# UNOSMD_V11.net
KiCad netlist of a schematic drawn in EAGLE
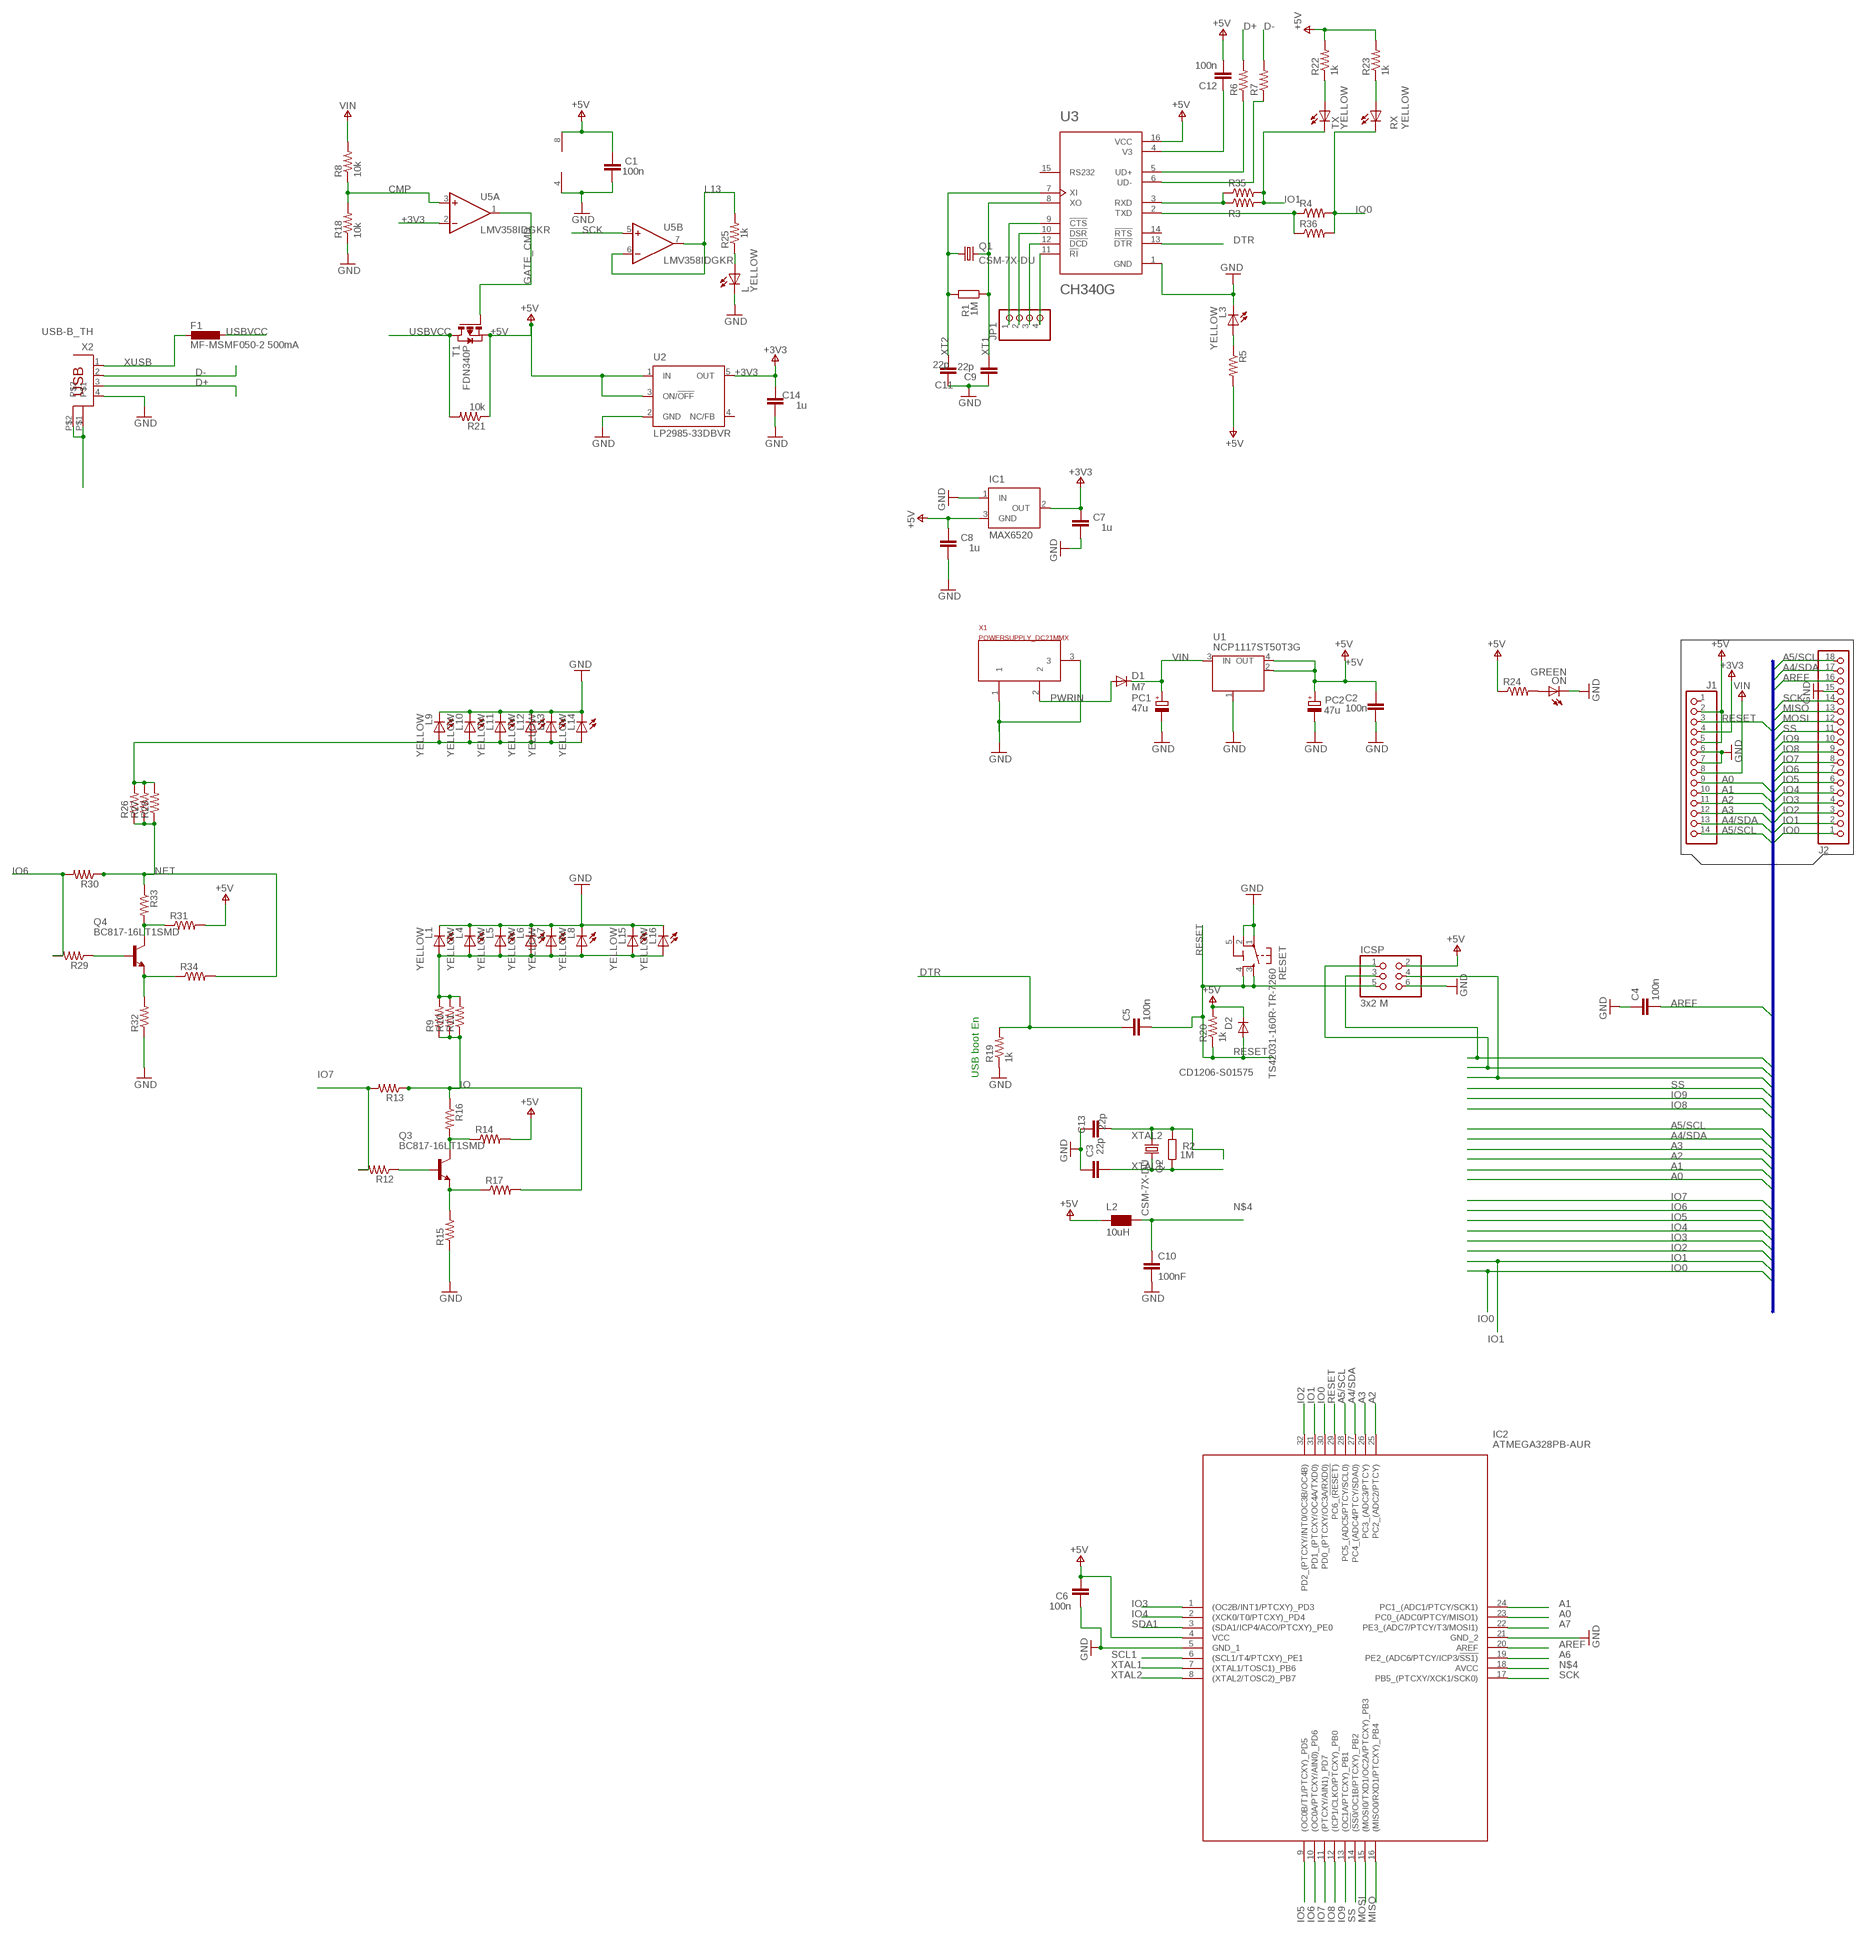
[diagram p0: schematic, sheet 1]

(export (version "E")
  (design (tool "Eeschema 10.0.6"))
  (components
    (comp (ref "C1")
      (value "100n")
      (footprint "eagle-import:C0603-ROUND")
      (libsource (lib "eagle-import") (part "C-EU0603-RND"))
    )
    (comp (ref "C2")
      (value "100n")
      (footprint "eagle-import:C0603-ROUND")
      (libsource (lib "eagle-import") (part "C-EU0603-RND"))
    )
    (comp (ref "C3")
      (value "22p")
      (footprint "eagle-import:C0603-ROUND")
      (libsource (lib "eagle-import") (part "C-EU0603-RND"))
    )
    (comp (ref "C4")
      (value "100n")
      (footprint "eagle-import:C0603-ROUND")
      (libsource (lib "eagle-import") (part "C-EU0603-RND"))
    )
    (comp (ref "C5")
      (value "100n")
      (footprint "eagle-import:C0603-ROUND")
      (libsource (lib "eagle-import") (part "C-EU0603-RND"))
    )
    (comp (ref "C6")
      (value "100n")
      (footprint "eagle-import:C0603-ROUND")
      (libsource (lib "eagle-import") (part "C-EU0603-RND"))
    )
    (comp (ref "C7")
      (value "1u")
      (footprint "eagle-import:C0603-ROUND")
      (libsource (lib "eagle-import") (part "C-EU0603-RND"))
    )
    (comp (ref "C8")
      (value "1u")
      (footprint "eagle-import:C0603-ROUND")
      (libsource (lib "eagle-import") (part "C-EU0603-RND"))
    )
    (comp (ref "C9")
      (value "22p")
      (footprint "eagle-import:C0603-ROUND")
      (libsource (lib "eagle-import") (part "C-EU0603-RND"))
    )
    (comp (ref "C10")
      (value "100nF")
      (footprint "eagle-import:C0603-ROUND")
      (fields (field (name "PART_NUMBER") "100nF_0603"))
      (libsource (lib "eagle-import") (part "0015_100NF_0603"))
    )
    (comp (ref "C11")
      (value "22p")
      (footprint "eagle-import:C0603-ROUND")
      (libsource (lib "eagle-import") (part "C-EU0603-RND"))
    )
    (comp (ref "C12")
      (value "100n")
      (footprint "eagle-import:C0603-ROUND")
      (libsource (lib "eagle-import") (part "C-EU0603-RND"))
    )
    (comp (ref "C13")
      (value "22p")
      (footprint "eagle-import:C0603-ROUND")
      (libsource (lib "eagle-import") (part "C-EU0603-RND"))
    )
    (comp (ref "C14")
      (value "1u")
      (footprint "eagle-import:C0603-ROUND")
      (libsource (lib "eagle-import") (part "C-EU0603-RND"))
    )
    (comp (ref "D1")
      (value "M7")
      (footprint "eagle-import:SMB")
      (libsource (lib "eagle-import") (part "DIODE-SMB"))
    )
    (comp (ref "D2")
      (value "CD1206-S01575")
      (footprint "eagle-import:MINIMELF")
      (libsource (lib "eagle-import") (part "DIODE-MINIMELF"))
    )
    (comp (ref "F1")
      (value "MF-MSMF050-2 500mA")
      (footprint "eagle-import:L1812")
      (libsource (lib "eagle-import") (part "L-EUL1812"))
    )
    (comp (ref "IC1")
      (value "MAX6520")
      (footprint "eagle-import:SOT23")
      (fields (field (name "MF") "MAXIM") (field (name "MPN") "MAX6520EUR-T"))
      (libsource (lib "eagle-import") (part "MAX6520"))
    )
    (comp (ref "IC2")
      (value "ATMEGA328PB-AUR")
      (footprint "eagle-import:QFP80P900X900X120-32N")
      (fields (field (name "MOUSER_PART_NUMBER") "556-ATMEGA328PB-AUR"))
      (libsource (lib "eagle-import") (part "ATMEGA328PB-AUR"))
    )
    (comp (ref "ICSP")
      (value "3x2 M")
      (footprint "eagle-import:2X03")
      (libsource (lib "eagle-import") (part "PINHD-2X3"))
    )
    (comp (ref "J1")
      (value "-")
      (footprint "eagle-import:1X14-CUSTOM")
      (libsource (lib "eagle-import") (part "PINHD-1X14-CUSTOM"))
    )
    (comp (ref "J2")
      (value "-")
      (footprint "eagle-import:1X18-CUSTOM")
      (libsource (lib "eagle-import") (part "PINHD-1X18"))
    )
    (comp (ref "JP1")
      (value "PINHD-1X4")
      (footprint "eagle-import:1X04")
      (libsource (lib "eagle-import") (part "PINHD-1X4"))
    )
    (comp (ref "L")
      (value "YELLOW")
      (footprint "eagle-import:CHIP-LED0805")
      (libsource (lib "eagle-import") (part "LEDCHIP-LED0805"))
    )
    (comp (ref "L1")
      (value "YELLOW")
      (footprint "eagle-import:CHIP-LED0805")
      (libsource (lib "eagle-import") (part "LEDCHIP-LED0805"))
    )
    (comp (ref "L2")
      (value "10uH")
      (footprint "eagle-import:0805")
      (fields (field (name "PART_NUMBER") "CV201210-100K"))
      (libsource (lib "eagle-import") (part "0715_CV201210-100K"))
    )
    (comp (ref "L3")
      (value "YELLOW")
      (footprint "eagle-import:CHIP-LED0805")
      (libsource (lib "eagle-import") (part "LEDCHIP-LED0805"))
    )
    (comp (ref "L4")
      (value "YELLOW")
      (footprint "eagle-import:CHIP-LED0805")
      (libsource (lib "eagle-import") (part "LEDCHIP-LED0805"))
    )
    (comp (ref "L5")
      (value "YELLOW")
      (footprint "eagle-import:CHIP-LED0805")
      (libsource (lib "eagle-import") (part "LEDCHIP-LED0805"))
    )
    (comp (ref "L6")
      (value "YELLOW")
      (footprint "eagle-import:CHIP-LED0805")
      (libsource (lib "eagle-import") (part "LEDCHIP-LED0805"))
    )
    (comp (ref "L7")
      (value "YELLOW")
      (footprint "eagle-import:CHIP-LED0805")
      (libsource (lib "eagle-import") (part "LEDCHIP-LED0805"))
    )
    (comp (ref "L8")
      (value "YELLOW")
      (footprint "eagle-import:CHIP-LED0805")
      (libsource (lib "eagle-import") (part "LEDCHIP-LED0805"))
    )
    (comp (ref "L9")
      (value "YELLOW")
      (footprint "eagle-import:CHIP-LED0805")
      (libsource (lib "eagle-import") (part "LEDCHIP-LED0805"))
    )
    (comp (ref "L10")
      (value "YELLOW")
      (footprint "eagle-import:CHIP-LED0805")
      (libsource (lib "eagle-import") (part "LEDCHIP-LED0805"))
    )
    (comp (ref "L11")
      (value "YELLOW")
      (footprint "eagle-import:CHIP-LED0805")
      (libsource (lib "eagle-import") (part "LEDCHIP-LED0805"))
    )
    (comp (ref "L12")
      (value "YELLOW")
      (footprint "eagle-import:CHIP-LED0805")
      (libsource (lib "eagle-import") (part "LEDCHIP-LED0805"))
    )
    (comp (ref "L13")
      (value "YELLOW")
      (footprint "eagle-import:CHIP-LED0805")
      (libsource (lib "eagle-import") (part "LEDCHIP-LED0805"))
    )
    (comp (ref "L14")
      (value "YELLOW")
      (footprint "eagle-import:CHIP-LED0805")
      (libsource (lib "eagle-import") (part "LEDCHIP-LED0805"))
    )
    (comp (ref "L15")
      (value "YELLOW")
      (footprint "eagle-import:CHIP-LED0805")
      (libsource (lib "eagle-import") (part "LEDCHIP-LED0805"))
    )
    (comp (ref "L16")
      (value "YELLOW")
      (footprint "eagle-import:CHIP-LED0805")
      (libsource (lib "eagle-import") (part "LEDCHIP-LED0805"))
    )
    (comp (ref "ON")
      (value "GREEN")
      (footprint "eagle-import:CHIP-LED0805")
      (libsource (lib "eagle-import") (part "LEDCHIP-LED0805"))
    )
    (comp (ref "PC1")
      (value "47u")
      (footprint "eagle-import:PANASONIC_D")
      (libsource (lib "eagle-import") (part "CPOL-EUD"))
    )
    (comp (ref "PC2")
      (value "47u")
      (footprint "eagle-import:PANASONIC_D")
      (libsource (lib "eagle-import") (part "CPOL-EUD"))
    )
    (comp (ref "Q1")
      (value "CSM-7X-DU")
      (footprint "eagle-import:CSM-7X-DU")
      (libsource (lib "eagle-import") (part "CSM-7X-DU"))
    )
    (comp (ref "Q2")
      (value "CSM-7X-DU")
      (footprint "eagle-import:CSM-7X-DU")
      (libsource (lib "eagle-import") (part "CSM-7X-DU"))
    )
    (comp (ref "Q3")
      (value "BC817-16LT1SMD")
      (footprint "eagle-import:SOT23-BEC")
      (libsource (lib "eagle-import") (part "BC817SMD-16LT1"))
    )
    (comp (ref "Q4")
      (value "BC817-16LT1SMD")
      (footprint "eagle-import:SOT23-BEC")
      (libsource (lib "eagle-import") (part "BC817SMD-16LT1"))
    )
    (comp (ref "R1")
      (value "1M")
      (footprint "eagle-import:R0603-ROUND")
      (libsource (lib "eagle-import") (part "R-EU_R0603"))
    )
    (comp (ref "R2")
      (value "1M")
      (footprint "eagle-import:R0603-ROUND")
      (libsource (lib "eagle-import") (part "R-EU_R0603"))
    )
    (comp (ref "R3")
      (value "R-US_R0603")
      (footprint "eagle-import:R0603")
      (libsource (lib "eagle-import") (part "R-US_R0603"))
    )
    (comp (ref "R4")
      (value "R-US_R0603")
      (footprint "eagle-import:R0603")
      (libsource (lib "eagle-import") (part "R-US_R0603"))
    )
    (comp (ref "R5")
      (value "R-US_R0603")
      (footprint "eagle-import:R0603")
      (libsource (lib "eagle-import") (part "R-US_R0603"))
    )
    (comp (ref "R6")
      (value "R-US_R0603")
      (footprint "eagle-import:R0603")
      (libsource (lib "eagle-import") (part "R-US_R0603"))
    )
    (comp (ref "R7")
      (value "R-US_R0603")
      (footprint "eagle-import:R0603")
      (libsource (lib "eagle-import") (part "R-US_R0603"))
    )
    (comp (ref "R8")
      (value "10k")
      (footprint "eagle-import:R0603")
      (libsource (lib "eagle-import") (part "R-US_R0603"))
    )
    (comp (ref "R9")
      (value "R-US_R0603")
      (footprint "eagle-import:R0603")
      (libsource (lib "eagle-import") (part "R-US_R0603"))
    )
    (comp (ref "R10")
      (value "R-US_R0603")
      (footprint "eagle-import:R0603")
      (libsource (lib "eagle-import") (part "R-US_R0603"))
    )
    (comp (ref "R11")
      (value "R-US_R0603")
      (footprint "eagle-import:R0603")
      (libsource (lib "eagle-import") (part "R-US_R0603"))
    )
    (comp (ref "R12")
      (value "R-US_R0603")
      (footprint "eagle-import:R0603")
      (libsource (lib "eagle-import") (part "R-US_R0603"))
    )
    (comp (ref "R13")
      (value "R-US_R0603")
      (footprint "eagle-import:R0603")
      (libsource (lib "eagle-import") (part "R-US_R0603"))
    )
    (comp (ref "R14")
      (value "R-US_R0603")
      (footprint "eagle-import:R0603")
      (libsource (lib "eagle-import") (part "R-US_R0603"))
    )
    (comp (ref "R15")
      (value "R-US_R0603")
      (footprint "eagle-import:R0603")
      (libsource (lib "eagle-import") (part "R-US_R0603"))
    )
    (comp (ref "R16")
      (value "R-US_R0603")
      (footprint "eagle-import:R0603")
      (libsource (lib "eagle-import") (part "R-US_R0603"))
    )
    (comp (ref "R17")
      (value "R-US_R0603")
      (footprint "eagle-import:R0603")
      (libsource (lib "eagle-import") (part "R-US_R0603"))
    )
    (comp (ref "R18")
      (value "10k")
      (footprint "eagle-import:R0603")
      (libsource (lib "eagle-import") (part "R-US_R0603"))
    )
    (comp (ref "R19")
      (value "1k")
      (footprint "eagle-import:R0603")
      (libsource (lib "eagle-import") (part "R-US_R0603"))
    )
    (comp (ref "R20")
      (value "1k")
      (footprint "eagle-import:R0603")
      (libsource (lib "eagle-import") (part "R-US_R0603"))
    )
    (comp (ref "R21")
      (value "10k")
      (footprint "eagle-import:R0603")
      (libsource (lib "eagle-import") (part "R-US_R0603"))
    )
    (comp (ref "R22")
      (value "1k")
      (footprint "eagle-import:R0603")
      (libsource (lib "eagle-import") (part "R-US_R0603"))
    )
    (comp (ref "R23")
      (value "1k")
      (footprint "eagle-import:R0603")
      (libsource (lib "eagle-import") (part "R-US_R0603"))
    )
    (comp (ref "R24")
      (value "R-US_R0603")
      (footprint "eagle-import:R0603")
      (libsource (lib "eagle-import") (part "R-US_R0603"))
    )
    (comp (ref "R25")
      (value "1k")
      (footprint "eagle-import:R0603")
      (libsource (lib "eagle-import") (part "R-US_R0603"))
    )
    (comp (ref "R26")
      (value "R-US_R0603")
      (footprint "eagle-import:R0603")
      (libsource (lib "eagle-import") (part "R-US_R0603"))
    )
    (comp (ref "R27")
      (value "R-US_R0603")
      (footprint "eagle-import:R0603")
      (libsource (lib "eagle-import") (part "R-US_R0603"))
    )
    (comp (ref "R28")
      (value "R-US_R0603")
      (footprint "eagle-import:R0603")
      (libsource (lib "eagle-import") (part "R-US_R0603"))
    )
    (comp (ref "R29")
      (value "R-US_R0603")
      (footprint "eagle-import:R0603")
      (libsource (lib "eagle-import") (part "R-US_R0603"))
    )
    (comp (ref "R30")
      (value "R-US_R0603")
      (footprint "eagle-import:R0603")
      (libsource (lib "eagle-import") (part "R-US_R0603"))
    )
    (comp (ref "R31")
      (value "R-US_R0603")
      (footprint "eagle-import:R0603")
      (libsource (lib "eagle-import") (part "R-US_R0603"))
    )
    (comp (ref "R32")
      (value "R-US_R0603")
      (footprint "eagle-import:R0603")
      (libsource (lib "eagle-import") (part "R-US_R0603"))
    )
    (comp (ref "R33")
      (value "R-US_R0603")
      (footprint "eagle-import:R0603")
      (libsource (lib "eagle-import") (part "R-US_R0603"))
    )
    (comp (ref "R34")
      (value "R-US_R0603")
      (footprint "eagle-import:R0603")
      (libsource (lib "eagle-import") (part "R-US_R0603"))
    )
    (comp (ref "R35")
      (value "R-US_R0603")
      (footprint "eagle-import:R0603")
      (libsource (lib "eagle-import") (part "R-US_R0603"))
    )
    (comp (ref "R36")
      (value "R-US_R0603")
      (footprint "eagle-import:R0603")
      (libsource (lib "eagle-import") (part "R-US_R0603"))
    )
    (comp (ref "RESET")
      (value "TS42031-160R-TR-7260")
      (footprint "eagle-import:TS42")
      (libsource (lib "eagle-import") (part "TS42"))
    )
    (comp (ref "RX")
      (value "YELLOW")
      (footprint "eagle-import:CHIP-LED0805")
      (libsource (lib "eagle-import") (part "LEDCHIP-LED0805"))
    )
    (comp (ref "T1")
      (value "FDN340P")
      (footprint "eagle-import:SOT-23")
      (libsource (lib "eagle-import") (part "PMOSSOT23"))
    )
    (comp (ref "TX")
      (value "YELLOW")
      (footprint "eagle-import:CHIP-LED0805")
      (libsource (lib "eagle-import") (part "LEDCHIP-LED0805"))
    )
    (comp (ref "U1")
      (value "NCP1117ST50T3G")
      (footprint "eagle-import:SOT223")
      (libsource (lib "eagle-import") (part "MC33269ST-3.3T3"))
    )
    (comp (ref "U2")
      (value "LP2985-33DBVR")
      (footprint "eagle-import:SOT23-DBV")
      (libsource (lib "eagle-import") (part "LP2985-XXDBVR33"))
    )
    (comp (ref "U3")
      (value "CH340G")
      (footprint "eagle-import:SOIC127P600X180-16N")
      (fields (field (name "MF") "WCH") (field (name "MP") "Ch340G"))
      (libsource (lib "eagle-import") (part "CH340G"))
    )
    (comp (ref "U5")
      (value "LMV358IDGKR")
      (footprint "eagle-import:MSOP08")
      (libsource (lib "eagle-import") (part "LMV358?MMX"))
    )
    (comp (ref "X1")
      (value "POWERSUPPLY_DC21MMX")
      (footprint "eagle-import:POWERSUPPLY_DC-21MM")
      (libsource (lib "eagle-import") (part "POWERSUPPLY_DC21MMX"))
    )
    (comp (ref "X2")
      (value "USB-B_TH")
      (footprint "eagle-import:PN61729")
      (libsource (lib "eagle-import") (part "PN61729"))
    )
  )
  (nets
    (net (code "1") (name "+3V3") (class "Default")
      (node (ref "C14") (pin "2") (pinfunction "2_2") (pintype "passive"))
      (node (ref "C7") (pin "2") (pinfunction "2_2") (pintype "passive"))
      (node (ref "IC1") (pin "2") (pinfunction "OUT_2") (pintype "output"))
      (node (ref "J1") (pin "4") (pinfunction "4_4") (pintype "passive"))
      (node (ref "U2") (pin "5") (pinfunction "OUT_5") (pintype "passive"))
      (node (ref "U5") (pin "2") (pinfunction "-IN_2") (pintype "input"))
    )
    (net (code "2") (name "+5V") (class "Default")
      (node (ref "C1") (pin "2") (pinfunction "2_2") (pintype "passive"))
      (node (ref "C12") (pin "2") (pinfunction "2_2") (pintype "passive"))
      (node (ref "C2") (pin "2") (pinfunction "2_2") (pintype "passive"))
      (node (ref "C6") (pin "2") (pinfunction "2_2") (pintype "passive"))
      (node (ref "C8") (pin "2") (pinfunction "2_2") (pintype "passive"))
      (node (ref "D2") (pin "C") (pinfunction "C_C") (pintype "passive"))
      (node (ref "IC1") (pin "3") (pinfunction "GND_3") (pintype "power_in"))
      (node (ref "IC2") (pin "4") (pinfunction "VCC_4") (pintype "bidirectional"))
      (node (ref "ICSP") (pin "2") (pinfunction "2_2") (pintype "passive"))
      (node (ref "J1") (pin "2") (pinfunction "2_2") (pintype "passive"))
      (node (ref "J1") (pin "5") (pinfunction "5_5") (pintype "passive"))
      (node (ref "L2") (pin "1") (pinfunction "1_1") (pintype "passive"))
      (node (ref "PC2") (pin "+") (pinfunction "+_+") (pintype "passive"))
      (node (ref "R14") (pin "2") (pinfunction "2_2") (pintype "passive"))
      (node (ref "R20") (pin "2") (pinfunction "2_2") (pintype "passive"))
      (node (ref "R21") (pin "1") (pinfunction "1_1") (pintype "passive"))
      (node (ref "R22") (pin "2") (pinfunction "2_2") (pintype "passive"))
      (node (ref "R23") (pin "2") (pinfunction "2_2") (pintype "passive"))
      (node (ref "R24") (pin "1") (pinfunction "1_1") (pintype "passive"))
      (node (ref "R31") (pin "2") (pinfunction "2_2") (pintype "passive"))
      (node (ref "R5") (pin "2") (pinfunction "2_2") (pintype "passive"))
      (node (ref "T1") (pin "2") (pinfunction "S_2") (pintype "passive"))
      (node (ref "U1") (pin "2") (pinfunction "OUT_2") (pintype "passive"))
      (node (ref "U1") (pin "4") (pinfunction "OUT_4") (pintype "passive"))
      (node (ref "U2") (pin "1") (pinfunction "IN_1") (pintype "input"))
      (node (ref "U2") (pin "3") (pinfunction "ON/~{OFF}_3") (pintype "input"))
      (node (ref "U3") (pin "16") (pinfunction "VCC_16") (pintype "power_in"))
      (node (ref "U5") (pin "8") (pinfunction "V+_8") (pintype "power_in"))
    )
    (net (code "3") (name "/5-GND") (class "Default")
      (node (ref "RESET") (pin "5") (pinfunction "5-GND_5") (pintype "power_in"))
    )
    (net (code "4") (name "/A0") (class "Default")
      (node (ref "IC2") (pin "23") (pinfunction "PC0_(ADC0/PTCY/MISO1)_23") (pintype "bidirectional"))
      (node (ref "J1") (pin "9") (pinfunction "9_9") (pintype "passive"))
    )
    (net (code "5") (name "/A1") (class "Default")
      (node (ref "IC2") (pin "24") (pinfunction "PC1_(ADC1/PTCY/SCK1)_24") (pintype "bidirectional"))
      (node (ref "J1") (pin "10") (pinfunction "10_10") (pintype "passive"))
    )
    (net (code "6") (name "/A2") (class "Default")
      (node (ref "IC2") (pin "25") (pinfunction "PC2_(ADC2/PTCY)_25") (pintype "bidirectional"))
      (node (ref "J1") (pin "11") (pinfunction "11_11") (pintype "passive"))
    )
    (net (code "7") (name "/A3") (class "Default")
      (node (ref "IC2") (pin "26") (pinfunction "PC3_(ADC3/PTCY)_26") (pintype "bidirectional"))
      (node (ref "J1") (pin "12") (pinfunction "12_12") (pintype "passive"))
    )
    (net (code "8") (name "/A4{slash}SDA") (class "Default")
      (node (ref "IC2") (pin "27") (pinfunction "PC4_(ADC4/PTCY/SDA0)_27") (pintype "bidirectional"))
      (node (ref "J1") (pin "13") (pinfunction "13_13") (pintype "passive"))
      (node (ref "J2") (pin "17") (pinfunction "17_17") (pintype "passive"))
    )
    (net (code "9") (name "/A5{slash}SCL") (class "Default")
      (node (ref "IC2") (pin "28") (pinfunction "PC5_(ADC5/PTCY/SCL0)_28") (pintype "bidirectional"))
      (node (ref "J1") (pin "14") (pinfunction "14_14") (pintype "passive"))
      (node (ref "J2") (pin "18") (pinfunction "18_18") (pintype "passive"))
    )
    (net (code "10") (name "/A6") (class "Default")
      (node (ref "IC2") (pin "19") (pinfunction "PE2_(ADC6/PTCY/ICP3/~{SS1})_19") (pintype "bidirectional"))
    )
    (net (code "11") (name "/A7") (class "Default")
      (node (ref "IC2") (pin "22") (pinfunction "PE3_(ADC7/PTCY/T3/MOSI1)_22") (pintype "bidirectional"))
    )
    (net (code "12") (name "/AREF") (class "Default")
      (node (ref "C4") (pin "2") (pinfunction "2_2") (pintype "passive"))
      (node (ref "IC2") (pin "20") (pinfunction "AREF_20") (pintype "bidirectional"))
      (node (ref "J2") (pin "16") (pinfunction "16_16") (pintype "passive"))
    )
    (net (code "13") (name "/CMP") (class "Default")
      (node (ref "R18") (pin "2") (pinfunction "2_2") (pintype "passive"))
      (node (ref "R8") (pin "1") (pinfunction "1_1") (pintype "passive"))
      (node (ref "U5") (pin "3") (pinfunction "+IN_3") (pintype "input"))
    )
    (net (code "14") (name "/D+") (class "Default")
      (node (ref "R6") (pin "2") (pinfunction "2_2") (pintype "passive"))
      (node (ref "X2") (pin "3") (pinfunction "3_3") (pintype "bidirectional"))
    )
    (net (code "15") (name "/D-") (class "Default")
      (node (ref "R7") (pin "2") (pinfunction "2_2") (pintype "passive"))
      (node (ref "X2") (pin "2") (pinfunction "2_2") (pintype "bidirectional"))
    )
    (net (code "16") (name "/DTR") (class "Default")
      (node (ref "C5") (pin "1") (pinfunction "1_1") (pintype "passive"))
      (node (ref "R19") (pin "2") (pinfunction "2_2") (pintype "passive"))
      (node (ref "U3") (pin "13") (pinfunction "~{DTR}_13") (pintype "output"))
    )
    (net (code "17") (name "/GATE_CMD") (class "Default")
      (node (ref "T1") (pin "3") (pinfunction "G_3") (pintype "passive"))
      (node (ref "U5") (pin "1") (pinfunction "OUT_1") (pintype "output"))
    )
    (net (code "18") (name "/IO") (class "Default")
      (node (ref "R10") (pin "1") (pinfunction "1_1") (pintype "passive"))
      (node (ref "R11") (pin "1") (pinfunction "1_1") (pintype "passive"))
      (node (ref "R13") (pin "1") (pinfunction "1_1") (pintype "passive"))
      (node (ref "R16") (pin "1") (pinfunction "1_1") (pintype "passive"))
      (node (ref "R17") (pin "2") (pinfunction "2_2") (pintype "passive"))
      (node (ref "R9") (pin "1") (pinfunction "1_1") (pintype "passive"))
    )
    (net (code "19") (name "/IO0") (class "Default")
      (node (ref "IC2") (pin "30") (pinfunction "PD0_(PTCXY/OC3A/RXD0)_30") (pintype "bidirectional"))
      (node (ref "J2") (pin "1") (pinfunction "1_1") (pintype "passive"))
      (node (ref "R36") (pin "2") (pinfunction "2_2") (pintype "passive"))
      (node (ref "R4") (pin "2") (pinfunction "2_2") (pintype "passive"))
      (node (ref "RX") (pin "C") (pinfunction "C_C") (pintype "passive"))
    )
    (net (code "20") (name "/IO1") (class "Default")
      (node (ref "IC2") (pin "31") (pinfunction "PD1_(PTCXY/OC4A/TXD0)_31") (pintype "bidirectional"))
      (node (ref "J2") (pin "2") (pinfunction "2_2") (pintype "passive"))
      (node (ref "R3") (pin "2") (pinfunction "2_2") (pintype "passive"))
      (node (ref "R35") (pin "2") (pinfunction "2_2") (pintype "passive"))
      (node (ref "TX") (pin "C") (pinfunction "C_C") (pintype "passive"))
    )
    (net (code "21") (name "/IO2") (class "Default")
      (node (ref "IC2") (pin "32") (pinfunction "PD2_(PTCXY/INT0/OC3B/OC4B)_32") (pintype "bidirectional"))
      (node (ref "J2") (pin "3") (pinfunction "3_3") (pintype "passive"))
    )
    (net (code "22") (name "/IO3") (class "Default")
      (node (ref "IC2") (pin "1") (pinfunction "(OC2B/INT1/PTCXY)_PD3_1") (pintype "bidirectional"))
      (node (ref "J2") (pin "4") (pinfunction "4_4") (pintype "passive"))
    )
    (net (code "23") (name "/IO4") (class "Default")
      (node (ref "IC2") (pin "2") (pinfunction "(XCK0/T0/PTCXY)_PD4_2") (pintype "bidirectional"))
      (node (ref "J2") (pin "5") (pinfunction "5_5") (pintype "passive"))
    )
    (net (code "24") (name "/IO5") (class "Default")
      (node (ref "IC2") (pin "9") (pinfunction "(OC0B/T1/PTCXY)_PD5_9") (pintype "bidirectional"))
      (node (ref "J2") (pin "6") (pinfunction "6_6") (pintype "passive"))
    )
    (net (code "25") (name "/IO6") (class "Default")
      (node (ref "IC2") (pin "10") (pinfunction "(OC0A/PTCXY/AIN0)_PD6_10") (pintype "bidirectional"))
      (node (ref "J2") (pin "7") (pinfunction "7_7") (pintype "passive"))
      (node (ref "R29") (pin "2") (pinfunction "2_2") (pintype "passive"))
      (node (ref "R30") (pin "2") (pinfunction "2_2") (pintype "passive"))
    )
    (net (code "26") (name "/IO7") (class "Default")
      (node (ref "IC2") (pin "11") (pinfunction "(PTCXY/AIN1)_PD7_11") (pintype "bidirectional"))
      (node (ref "J2") (pin "8") (pinfunction "8_8") (pintype "passive"))
      (node (ref "R12") (pin "2") (pinfunction "2_2") (pintype "passive"))
      (node (ref "R13") (pin "2") (pinfunction "2_2") (pintype "passive"))
    )
    (net (code "27") (name "/IO8") (class "Default")
      (node (ref "IC2") (pin "12") (pinfunction "(ICP1/CLKO/PTCXY)_PB0_12") (pintype "bidirectional"))
      (node (ref "J2") (pin "9") (pinfunction "9_9") (pintype "passive"))
    )
    (net (code "28") (name "/IO9") (class "Default")
      (node (ref "IC2") (pin "13") (pinfunction "(OC1A/PTCXY)_PB1_13") (pintype "bidirectional"))
      (node (ref "J2") (pin "10") (pinfunction "10_10") (pintype "passive"))
    )
    (net (code "29") (name "/L13") (class "Default")
      (node (ref "R25") (pin "2") (pinfunction "2_2") (pintype "passive"))
      (node (ref "U5") (pin "6") (pinfunction "-IN_6") (pintype "input"))
      (node (ref "U5") (pin "7") (pinfunction "OUT_7") (pintype "output"))
    )
    (net (code "30") (name "/MISO") (class "Default")
      (node (ref "IC2") (pin "16") (pinfunction "(MISO0/RXD1/PTCXY)_PB4_16") (pintype "bidirectional"))
      (node (ref "ICSP") (pin "1") (pinfunction "1_1") (pintype "passive"))
      (node (ref "J2") (pin "13") (pinfunction "13_13") (pintype "passive"))
    )
    (net (code "31") (name "/MOSI") (class "Default")
      (node (ref "IC2") (pin "15") (pinfunction "(MOSI0/TXD1/OC2A/PTCXY)_PB3_15") (pintype "bidirectional"))
      (node (ref "ICSP") (pin "4") (pinfunction "4_4") (pintype "passive"))
      (node (ref "J2") (pin "12") (pinfunction "12_12") (pintype "passive"))
    )
    (net (code "32") (name "/N$4") (class "Default")
      (node (ref "C10") (pin "1") (pinfunction "1_1") (pintype "passive"))
      (node (ref "IC2") (pin "18") (pinfunction "AVCC_18") (pintype "bidirectional"))
      (node (ref "L2") (pin "2") (pinfunction "2_2") (pintype "passive"))
    )
    (net (code "33") (name "/NET") (class "Default")
      (node (ref "R26") (pin "1") (pinfunction "1_1") (pintype "passive"))
      (node (ref "R27") (pin "1") (pinfunction "1_1") (pintype "passive"))
      (node (ref "R28") (pin "1") (pinfunction "1_1") (pintype "passive"))
      (node (ref "R30") (pin "1") (pinfunction "1_1") (pintype "passive"))
      (node (ref "R33") (pin "1") (pinfunction "1_1") (pintype "passive"))
      (node (ref "R34") (pin "2") (pinfunction "2_2") (pintype "passive"))
    )
    (net (code "34") (name "/PWRIN") (class "Default")
      (node (ref "D1") (pin "A") (pinfunction "A_A") (pintype "passive"))
      (node (ref "X1") (pin "2") (pinfunction "2_2") (pintype "power_in"))
    )
    (net (code "35") (name "/RESET") (class "Default")
      (node (ref "C5") (pin "2") (pinfunction "2_2") (pintype "passive"))
      (node (ref "D2") (pin "A") (pinfunction "A_A") (pintype "passive"))
      (node (ref "IC2") (pin "29") (pinfunction "PC6_(~{RESET})_29") (pintype "bidirectional"))
      (node (ref "ICSP") (pin "5") (pinfunction "5_5") (pintype "passive"))
      (node (ref "J1") (pin "3") (pinfunction "3_3") (pintype "passive"))
      (node (ref "R20") (pin "1") (pinfunction "1_1") (pintype "passive"))
      (node (ref "RESET") (pin "3") (pinfunction "3_3") (pintype "passive"))
      (node (ref "RESET") (pin "4") (pinfunction "4_4") (pintype "passive"))
    )
    (net (code "36") (name "/SCK") (class "Default")
      (node (ref "IC2") (pin "17") (pinfunction "PB5_(PTCXY/XCK1/SCK0)_17") (pintype "bidirectional"))
      (node (ref "ICSP") (pin "3") (pinfunction "3_3") (pintype "passive"))
      (node (ref "J2") (pin "14") (pinfunction "14_14") (pintype "passive"))
      (node (ref "U5") (pin "5") (pinfunction "+IN_5") (pintype "input"))
    )
    (net (code "37") (name "/SCL1") (class "Default")
      (node (ref "IC2") (pin "6") (pinfunction "(SCL1/T4/PTCXY)_PE1_6") (pintype "bidirectional"))
    )
    (net (code "38") (name "/SDA1") (class "Default")
      (node (ref "IC2") (pin "3") (pinfunction "(SDA1/ICP4/ACO/PTCXY)_PE0_3") (pintype "bidirectional"))
    )
    (net (code "39") (name "/SS") (class "Default")
      (node (ref "IC2") (pin "14") (pinfunction "(~{SS0}/OC1B/PTCXY)_PB2_14") (pintype "bidirectional"))
      (node (ref "J2") (pin "11") (pinfunction "11_11") (pintype "passive"))
    )
    (net (code "40") (name "/USBVCC") (class "Default")
      (node (ref "F1") (pin "1") (pinfunction "1_1") (pintype "passive"))
      (node (ref "R21") (pin "2") (pinfunction "2_2") (pintype "passive"))
      (node (ref "T1") (pin "1") (pinfunction "D_1") (pintype "passive"))
    )
    (net (code "41") (name "/XT1") (class "Default")
      (node (ref "C9") (pin "1") (pinfunction "1_1") (pintype "passive"))
      (node (ref "Q1") (pin "2") (pinfunction "2_2") (pintype "passive"))
      (node (ref "R1") (pin "1") (pinfunction "1_1") (pintype "passive"))
      (node (ref "U3") (pin "8") (pinfunction "XO_8") (pintype "output"))
    )
    (net (code "42") (name "/XT2") (class "Default")
      (node (ref "C11") (pin "1") (pinfunction "1_1") (pintype "passive"))
      (node (ref "Q1") (pin "1") (pinfunction "1_1") (pintype "passive"))
      (node (ref "R1") (pin "2") (pinfunction "2_2") (pintype "passive"))
      (node (ref "U3") (pin "7") (pinfunction "XI_7") (pintype "input"))
    )
    (net (code "43") (name "/XTAL1") (class "Default")
      (node (ref "C3") (pin "1") (pinfunction "1_1") (pintype "passive"))
      (node (ref "IC2") (pin "7") (pinfunction "(XTAL1/TOSC1)_PB6_7") (pintype "bidirectional"))
      (node (ref "Q2") (pin "2") (pinfunction "2_2") (pintype "passive"))
      (node (ref "R2") (pin "1") (pinfunction "1_1") (pintype "passive"))
    )
    (net (code "44") (name "/XTAL2") (class "Default")
      (node (ref "C13") (pin "1") (pinfunction "1_1") (pintype "passive"))
      (node (ref "IC2") (pin "8") (pinfunction "(XTAL2/TOSC2)_PB7_8") (pintype "bidirectional"))
      (node (ref "Q2") (pin "1") (pinfunction "1_1") (pintype "passive"))
      (node (ref "R2") (pin "2") (pinfunction "2_2") (pintype "passive"))
    )
    (net (code "45") (name "/XUSB") (class "Default")
      (node (ref "F1") (pin "2") (pinfunction "2_2") (pintype "passive"))
      (node (ref "X2") (pin "1") (pinfunction "1_1") (pintype "bidirectional"))
    )
    (net (code "46") (name "GND") (class "Default")
      (node (ref "C1") (pin "1") (pinfunction "1_1") (pintype "passive"))
      (node (ref "C10") (pin "2") (pinfunction "2_2") (pintype "passive"))
      (node (ref "C11") (pin "2") (pinfunction "2_2") (pintype "passive"))
      (node (ref "C13") (pin "2") (pinfunction "2_2") (pintype "passive"))
      (node (ref "C14") (pin "1") (pinfunction "1_1") (pintype "passive"))
      (node (ref "C2") (pin "1") (pinfunction "1_1") (pintype "passive"))
      (node (ref "C3") (pin "2") (pinfunction "2_2") (pintype "passive"))
      (node (ref "C4") (pin "1") (pinfunction "1_1") (pintype "passive"))
      (node (ref "C6") (pin "1") (pinfunction "1_1") (pintype "passive"))
      (node (ref "C7") (pin "1") (pinfunction "1_1") (pintype "passive"))
      (node (ref "C8") (pin "1") (pinfunction "1_1") (pintype "passive"))
      (node (ref "C9") (pin "2") (pinfunction "2_2") (pintype "passive"))
      (node (ref "IC1") (pin "1") (pinfunction "IN_1") (pintype "input"))
      (node (ref "IC2") (pin "21") (pinfunction "GND_2_21") (pintype "bidirectional"))
      (node (ref "IC2") (pin "5") (pinfunction "GND_1_5") (pintype "bidirectional"))
      (node (ref "ICSP") (pin "6") (pinfunction "6_6") (pintype "passive"))
      (node (ref "J1") (pin "6") (pinfunction "6_6") (pintype "passive"))
      (node (ref "J1") (pin "7") (pinfunction "7_7") (pintype "passive"))
      (node (ref "J2") (pin "15") (pinfunction "15_15") (pintype "passive"))
      (node (ref "L") (pin "C") (pinfunction "C_C") (pintype "passive"))
      (node (ref "L1") (pin "C") (pinfunction "C_C") (pintype "passive"))
      (node (ref "L10") (pin "C") (pinfunction "C_C") (pintype "passive"))
      (node (ref "L11") (pin "C") (pinfunction "C_C") (pintype "passive"))
      (node (ref "L12") (pin "C") (pinfunction "C_C") (pintype "passive"))
      (node (ref "L13") (pin "C") (pinfunction "C_C") (pintype "passive"))
      (node (ref "L14") (pin "C") (pinfunction "C_C") (pintype "passive"))
      (node (ref "L15") (pin "C") (pinfunction "C_C") (pintype "passive"))
      (node (ref "L16") (pin "C") (pinfunction "C_C") (pintype "passive"))
      (node (ref "L3") (pin "C") (pinfunction "C_C") (pintype "passive"))
      (node (ref "L4") (pin "C") (pinfunction "C_C") (pintype "passive"))
      (node (ref "L5") (pin "C") (pinfunction "C_C") (pintype "passive"))
      (node (ref "L6") (pin "C") (pinfunction "C_C") (pintype "passive"))
      (node (ref "L7") (pin "C") (pinfunction "C_C") (pintype "passive"))
      (node (ref "L8") (pin "C") (pinfunction "C_C") (pintype "passive"))
      (node (ref "L9") (pin "C") (pinfunction "C_C") (pintype "passive"))
      (node (ref "ON") (pin "C") (pinfunction "C_C") (pintype "passive"))
      (node (ref "PC1") (pin "-") (pinfunction "-_-") (pintype "passive"))
      (node (ref "PC2") (pin "-") (pinfunction "-_-") (pintype "passive"))
      (node (ref "R15") (pin "1") (pinfunction "1_1") (pintype "passive"))
      (node (ref "R18") (pin "1") (pinfunction "1_1") (pintype "passive"))
      (node (ref "R19") (pin "1") (pinfunction "1_1") (pintype "passive"))
      (node (ref "R32") (pin "1") (pinfunction "1_1") (pintype "passive"))
      (node (ref "RESET") (pin "1") (pinfunction "1_1") (pintype "passive"))
      (node (ref "RESET") (pin "2") (pinfunction "2_2") (pintype "passive"))
      (node (ref "U1") (pin "1") (pinfunction "GND/ADJ_1") (pintype "input"))
      (node (ref "U2") (pin "2") (pinfunction "GND_2") (pintype "power_in"))
      (node (ref "U3") (pin "1") (pinfunction "GND_1") (pintype "power_in"))
      (node (ref "U5") (pin "4") (pinfunction "V-_4") (pintype "power_in"))
      (node (ref "X1") (pin "1") (pinfunction "1_1") (pintype "power_in"))
      (node (ref "X1") (pin "3") (pinfunction "3_3") (pintype "power_in"))
      (node (ref "X2") (pin "4") (pinfunction "4_4") (pintype "bidirectional"))
    )
    (net (code "47") (name "Net-(L-PadA)") (class "Default")
      (node (ref "L") (pin "A") (pinfunction "A_A") (pintype "passive"))
      (node (ref "R25") (pin "1") (pinfunction "1_1") (pintype "passive"))
    )
    (net (code "48") (name "Net-(L1-PadA)") (class "Default")
      (node (ref "L1") (pin "A") (pinfunction "A_A") (pintype "passive"))
      (node (ref "L15") (pin "A") (pinfunction "A_A") (pintype "passive"))
      (node (ref "L16") (pin "A") (pinfunction "A_A") (pintype "passive"))
      (node (ref "L4") (pin "A") (pinfunction "A_A") (pintype "passive"))
      (node (ref "L5") (pin "A") (pinfunction "A_A") (pintype "passive"))
      (node (ref "L6") (pin "A") (pinfunction "A_A") (pintype "passive"))
      (node (ref "L7") (pin "A") (pinfunction "A_A") (pintype "passive"))
      (node (ref "L8") (pin "A") (pinfunction "A_A") (pintype "passive"))
      (node (ref "R10") (pin "2") (pinfunction "2_2") (pintype "passive"))
      (node (ref "R11") (pin "2") (pinfunction "2_2") (pintype "passive"))
      (node (ref "R9") (pin "2") (pinfunction "2_2") (pintype "passive"))
    )
    (net (code "49") (name "Net-(L3-PadA)") (class "Default")
      (node (ref "L3") (pin "A") (pinfunction "A_A") (pintype "passive"))
      (node (ref "R5") (pin "1") (pinfunction "1_1") (pintype "passive"))
    )
    (net (code "50") (name "Net-(L10-PadA)") (class "Default")
      (node (ref "L10") (pin "A") (pinfunction "A_A") (pintype "passive"))
      (node (ref "L11") (pin "A") (pinfunction "A_A") (pintype "passive"))
      (node (ref "L12") (pin "A") (pinfunction "A_A") (pintype "passive"))
      (node (ref "L13") (pin "A") (pinfunction "A_A") (pintype "passive"))
      (node (ref "L14") (pin "A") (pinfunction "A_A") (pintype "passive"))
      (node (ref "L9") (pin "A") (pinfunction "A_A") (pintype "passive"))
      (node (ref "R26") (pin "2") (pinfunction "2_2") (pintype "passive"))
      (node (ref "R27") (pin "2") (pinfunction "2_2") (pintype "passive"))
      (node (ref "R28") (pin "2") (pinfunction "2_2") (pintype "passive"))
    )
    (net (code "51") (name "Net-(ON-PadA)") (class "Default")
      (node (ref "ON") (pin "A") (pinfunction "A_A") (pintype "passive"))
      (node (ref "R24") (pin "2") (pinfunction "2_2") (pintype "passive"))
    )
    (net (code "52") (name "Net-(Q3-PadB)") (class "Default")
      (node (ref "Q3") (pin "B") (pinfunction "B_B") (pintype "passive"))
      (node (ref "R12") (pin "1") (pinfunction "1_1") (pintype "passive"))
    )
    (net (code "53") (name "Net-(Q3-PadC)") (class "Default")
      (node (ref "Q3") (pin "C") (pinfunction "C_C") (pintype "passive"))
      (node (ref "R14") (pin "1") (pinfunction "1_1") (pintype "passive"))
      (node (ref "R16") (pin "2") (pinfunction "2_2") (pintype "passive"))
    )
    (net (code "54") (name "Net-(Q3-PadE)") (class "Default")
      (node (ref "Q3") (pin "E") (pinfunction "E_E") (pintype "passive"))
      (node (ref "R15") (pin "2") (pinfunction "2_2") (pintype "passive"))
      (node (ref "R17") (pin "1") (pinfunction "1_1") (pintype "passive"))
    )
    (net (code "55") (name "Net-(Q4-PadB)") (class "Default")
      (node (ref "Q4") (pin "B") (pinfunction "B_B") (pintype "passive"))
      (node (ref "R29") (pin "1") (pinfunction "1_1") (pintype "passive"))
    )
    (net (code "56") (name "Net-(Q4-PadC)") (class "Default")
      (node (ref "Q4") (pin "C") (pinfunction "C_C") (pintype "passive"))
      (node (ref "R31") (pin "1") (pinfunction "1_1") (pintype "passive"))
      (node (ref "R33") (pin "2") (pinfunction "2_2") (pintype "passive"))
    )
    (net (code "57") (name "Net-(Q4-PadE)") (class "Default")
      (node (ref "Q4") (pin "E") (pinfunction "E_E") (pintype "passive"))
      (node (ref "R32") (pin "2") (pinfunction "2_2") (pintype "passive"))
      (node (ref "R34") (pin "1") (pinfunction "1_1") (pintype "passive"))
    )
    (net (code "58") (name "Net-(R22-Pad1)") (class "Default")
      (node (ref "R22") (pin "1") (pinfunction "1_1") (pintype "passive"))
      (node (ref "TX") (pin "A") (pinfunction "A_A") (pintype "passive"))
    )
    (net (code "59") (name "Net-(R23-Pad1)") (class "Default")
      (node (ref "R23") (pin "1") (pinfunction "1_1") (pintype "passive"))
      (node (ref "RX") (pin "A") (pinfunction "A_A") (pintype "passive"))
    )
    (net (code "60") (name "Net-(U3-RXD)") (class "Default")
      (node (ref "R3") (pin "1") (pinfunction "1_1") (pintype "passive"))
      (node (ref "R35") (pin "1") (pinfunction "1_1") (pintype "passive"))
      (node (ref "U3") (pin "3") (pinfunction "RXD_3") (pintype "input"))
    )
    (net (code "61") (name "Net-(U3-TXD)") (class "Default")
      (node (ref "R36") (pin "1") (pinfunction "1_1") (pintype "passive"))
      (node (ref "R4") (pin "1") (pinfunction "1_1") (pintype "passive"))
      (node (ref "U3") (pin "2") (pinfunction "TXD_2") (pintype "output"))
    )
    (net (code "62") (name "Net-(U3-UD+)") (class "Default")
      (node (ref "R6") (pin "1") (pinfunction "1_1") (pintype "passive"))
      (node (ref "U3") (pin "5") (pinfunction "UD+_5") (pintype "bidirectional"))
    )
    (net (code "63") (name "Net-(U3-UD-)") (class "Default")
      (node (ref "R7") (pin "1") (pinfunction "1_1") (pintype "passive"))
      (node (ref "U3") (pin "6") (pinfunction "UD-_6") (pintype "bidirectional"))
    )
    (net (code "64") (name "Net-(U3-V3)") (class "Default")
      (node (ref "C12") (pin "1") (pinfunction "1_1") (pintype "passive"))
      (node (ref "U3") (pin "4") (pinfunction "V3_4") (pintype "power_in"))
    )
    (net (code "65") (name "Net-(U3-~{CTS})") (class "Default")
      (node (ref "JP1") (pin "1") (pinfunction "1_1") (pintype "passive"))
      (node (ref "U3") (pin "9") (pinfunction "~{CTS}_9") (pintype "input"))
    )
    (net (code "66") (name "Net-(U3-~{DCD})") (class "Default")
      (node (ref "JP1") (pin "3") (pinfunction "3_3") (pintype "passive"))
      (node (ref "U3") (pin "12") (pinfunction "~{DCD}_12") (pintype "input"))
    )
    (net (code "67") (name "Net-(U3-~{DSR})") (class "Default")
      (node (ref "JP1") (pin "2") (pinfunction "2_2") (pintype "passive"))
      (node (ref "U3") (pin "10") (pinfunction "~{DSR}_10") (pintype "input"))
    )
    (net (code "68") (name "Net-(U3-~{RI})") (class "Default")
      (node (ref "JP1") (pin "4") (pinfunction "4_4") (pintype "passive"))
      (node (ref "U3") (pin "11") (pinfunction "~{RI}_11") (pintype "input"))
    )
    (net (code "69") (name "Net-(X2-PadP$1)") (class "Default")
      (node (ref "X2") (pin "P$1") (pinfunction "P$1_P$1") (pintype "bidirectional"))
      (node (ref "X2") (pin "P$2") (pinfunction "P$2_P$2") (pintype "bidirectional"))
    )
    (net (code "70") (name "VIN") (class "Default")
      (node (ref "D1") (pin "C") (pinfunction "C_C") (pintype "passive"))
      (node (ref "J1") (pin "8") (pinfunction "8_8") (pintype "passive"))
      (node (ref "PC1") (pin "+") (pinfunction "+_+") (pintype "passive"))
      (node (ref "R8") (pin "2") (pinfunction "2_2") (pintype "passive"))
      (node (ref "U1") (pin "3") (pinfunction "IN_3") (pintype "input"))
    )
    (net (code "71") (name "unconnected-(J1-Pad1)") (class "Default")
      (node (ref "J1") (pin "1") (pinfunction "1_1") (pintype "passive"))
    )
    (net (code "72") (name "unconnected-(U2-NC{slash}FB-Pad4)") (class "Default")
      (node (ref "U2") (pin "4") (pinfunction "NC/FB_4") (pintype "passive"))
    )
    (net (code "73") (name "unconnected-(U3-RS232-Pad15)") (class "Default")
      (node (ref "U3") (pin "15") (pinfunction "RS232_15") (pintype "input"))
    )
    (net (code "74") (name "unconnected-(U3-~{RTS}-Pad14)") (class "Default")
      (node (ref "U3") (pin "14") (pinfunction "~{RTS}_14") (pintype "output"))
    )
  )
)
